# mcu.net
KiCad netlist of a schematic drawn in Altium Designer
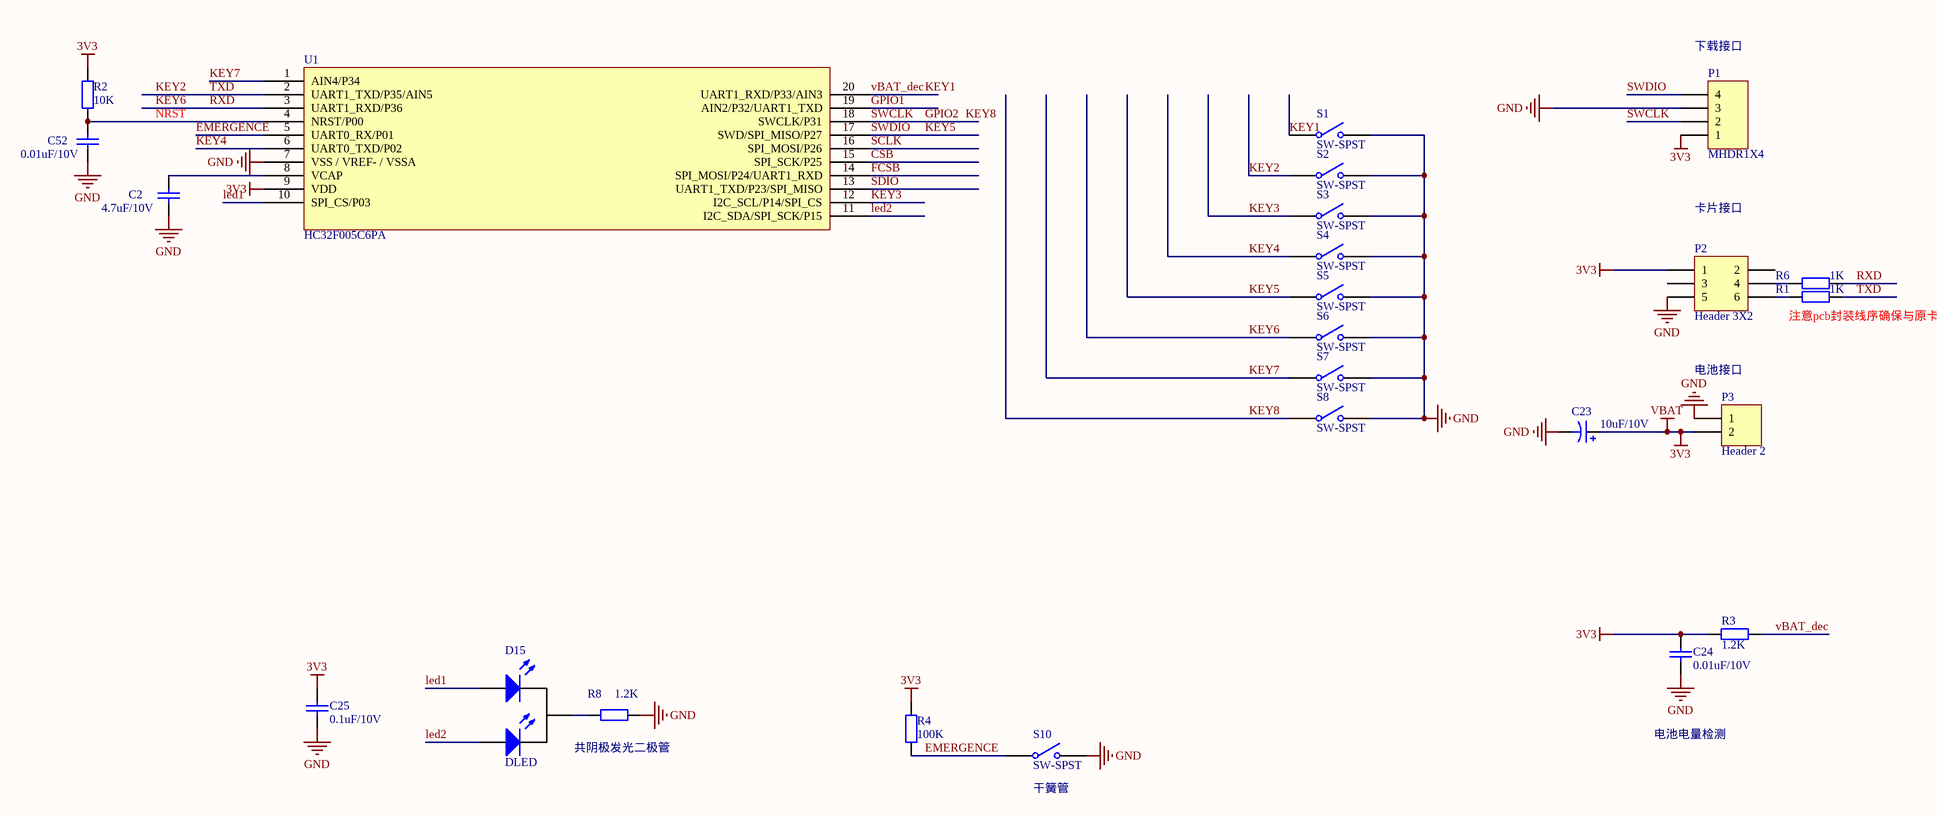
[diagram p0: mcu.SchDoc]

(export (version "E")
  (design (tool "Eeschema 10.0.6"))
  (components
    (comp (ref "C2")
      (value "4.7uF/10V")
      (footprint "0603C")
      (description "Capacitor")
      (fields (field (name "PUBLISHER") "Altium Limited"))
      (libsource (lib "Miscellaneous Devices") (part "Cap"))
    )
    (comp (ref "C23")
      (value "10uF/10V")
      (description "Polarized Capacitor (Radial)")
      (fields (field (name "PUBLISHER") "Altium Limited"))
      (libsource (lib "Miscellaneous Devices") (part "Cap Pol1"))
    )
    (comp (ref "C24")
      (value "0.01uF/10V")
      (footprint "0603C")
      (description "Capacitor")
      (fields (field (name "PUBLISHER") "Altium Limited"))
      (libsource (lib "Miscellaneous Devices") (part "Cap"))
    )
    (comp (ref "C25")
      (value "0.1uF/10V")
      (footprint "0603C")
      (description "Capacitor")
      (fields (field (name "PUBLISHER") "Altium Limited"))
      (libsource (lib "Miscellaneous Devices") (part "Cap"))
    )
    (comp (ref "C52")
      (value "0.01uF/10V")
      (footprint "0603C")
      (description "Capacitor")
      (fields (field (name "PUBLISHER") "Altium Limited"))
      (libsource (lib "Miscellaneous Devices") (part "Cap"))
    )
    (comp (ref "D15") (value "DLED") (libsource (lib "Schlib_20110825") (part "DLED")))
    (comp (ref "P1")
      (value "MHDR1X4")
      (footprint "SIP4")
      (description "Header, 4-Pin")
      (fields (field (name "PUBLISHER") "Altium Limited"))
      (libsource (lib "Miscellaneous Connectors") (part "MHDR1X4"))
    )
    (comp (ref "P2")
      (value "Header 3X2")
      (description "Header, 3-Pin, Dual row")
      (fields (field (name "PUBLISHER") "Altium Limited"))
      (libsource (lib "Miscellaneous Connectors") (part "Header 3X2"))
    )
    (comp (ref "P3")
      (value "Header 2")
      (description "Header, 2-Pin")
      (fields (field (name "PUBLISHER") "Altium Limited"))
      (libsource (lib "Miscellaneous Connectors") (part "Header 2"))
    )
    (comp (ref "R1")
      (value "1K")
      (footprint "0603R")
      (description "Resistor")
      (fields (field (name "PUBLISHER") "Altium Limited"))
      (libsource (lib "") (part "Res2_1"))
    )
    (comp (ref "R2")
      (value "10K")
      (footprint "0603R")
      (description "Resistor")
      (fields (field (name "PUBLISHER") "Altium Limited"))
      (libsource (lib "") (part "Res2_2"))
    )
    (comp (ref "R3")
      (value "1.2K")
      (footprint "0603R")
      (description "Resistor")
      (fields (field (name "PUBLISHER") "Altium Limited"))
      (libsource (lib "") (part "Res2_1"))
    )
    (comp (ref "R4")
      (value "100K")
      (footprint "0603R")
      (description "Resistor")
      (fields (field (name "PUBLISHER") "Altium Limited"))
      (libsource (lib "Miscellaneous Devices") (part "Res2"))
    )
    (comp (ref "R6")
      (value "1K")
      (footprint "0603R")
      (description "Resistor")
      (fields (field (name "PUBLISHER") "Altium Limited"))
      (libsource (lib "") (part "Res2_1"))
    )
    (comp (ref "R8")
      (value "1.2K")
      (footprint "0603R")
      (description "Resistor")
      (fields (field (name "PUBLISHER") "Altium Limited"))
      (libsource (lib "") (part "Res2_1"))
    )
    (comp (ref "S1")
      (value "SW-SPST")
      (description "Single-Pole, Single-Throw Switch")
      (fields (field (name "PUBLISHER") "Altium Limited"))
      (libsource (lib "Miscellaneous Devices") (part "SW-SPST"))
    )
    (comp (ref "S2")
      (value "SW-SPST")
      (description "Single-Pole, Single-Throw Switch")
      (fields (field (name "PUBLISHER") "Altium Limited"))
      (libsource (lib "Miscellaneous Devices") (part "SW-SPST"))
    )
    (comp (ref "S3")
      (value "SW-SPST")
      (description "Single-Pole, Single-Throw Switch")
      (fields (field (name "PUBLISHER") "Altium Limited"))
      (libsource (lib "Miscellaneous Devices") (part "SW-SPST"))
    )
    (comp (ref "S4")
      (value "SW-SPST")
      (description "Single-Pole, Single-Throw Switch")
      (fields (field (name "PUBLISHER") "Altium Limited"))
      (libsource (lib "Miscellaneous Devices") (part "SW-SPST"))
    )
    (comp (ref "S5")
      (value "SW-SPST")
      (description "Single-Pole, Single-Throw Switch")
      (fields (field (name "PUBLISHER") "Altium Limited"))
      (libsource (lib "Miscellaneous Devices") (part "SW-SPST"))
    )
    (comp (ref "S6")
      (value "SW-SPST")
      (description "Single-Pole, Single-Throw Switch")
      (fields (field (name "PUBLISHER") "Altium Limited"))
      (libsource (lib "Miscellaneous Devices") (part "SW-SPST"))
    )
    (comp (ref "S7")
      (value "SW-SPST")
      (description "Single-Pole, Single-Throw Switch")
      (fields (field (name "PUBLISHER") "Altium Limited"))
      (libsource (lib "Miscellaneous Devices") (part "SW-SPST"))
    )
    (comp (ref "S8")
      (value "SW-SPST")
      (description "Single-Pole, Single-Throw Switch")
      (fields (field (name "PUBLISHER") "Altium Limited"))
      (libsource (lib "Miscellaneous Devices") (part "SW-SPST"))
    )
    (comp (ref "S10")
      (value "SW-SPST")
      (description "Single-Pole, Single-Throw Switch")
      (fields (field (name "PUBLISHER") "Altium Limited"))
      (libsource (lib "Miscellaneous Devices") (part "SW-SPST"))
    )
    (comp (ref "U1") (value "HC32F005C6PA") (libsource (lib "Schlib_20110825") (part "HC32F005C6PA")))
  )
  (nets
    (net (code "1") (name "/CSB") (class "Default")
      (node (ref "U1") (pin "15") (pinfunction "SPI_SCK/P25_15") (pintype "passive"))
    )
    (net (code "2") (name "/EMERGENCE") (class "Default")
      (node (ref "R4") (pin "2") (pinfunction "2_2") (pintype "passive"))
      (node (ref "S10") (pin "1") (pinfunction "COMMON_1") (pintype "passive"))
      (node (ref "U1") (pin "5") (pinfunction "UART0_RX/P01_5") (pintype "passive"))
    )
    (net (code "3") (name "/FCSB") (class "Default")
      (node (ref "U1") (pin "14") (pinfunction "SPI_MOSI/P24/UART1_RXD_14") (pintype "passive"))
    )
    (net (code "4") (name "/GPIO1") (class "Default")
      (node (ref "U1") (pin "19") (pinfunction "AIN2/P32/UART1_TXD_19") (pintype "passive"))
    )
    (net (code "5") (name "/GPIO2") (class "Default")
      (node (ref "P1") (pin "2") (pinfunction "2_2") (pintype "passive"))
      (node (ref "S8") (pin "1") (pinfunction "COMMON_1") (pintype "passive"))
      (node (ref "U1") (pin "18") (pinfunction "SWCLK/P31_18") (pintype "passive"))
    )
    (net (code "6") (name "/KEY1") (class "Default")
      (node (ref "R3") (pin "1") (pinfunction "1_1") (pintype "passive"))
      (node (ref "S1") (pin "1") (pinfunction "COMMON_1") (pintype "passive"))
      (node (ref "U1") (pin "20") (pinfunction "UART1_RXD/P33/AIN3_20") (pintype "passive"))
    )
    (net (code "7") (name "/KEY2") (class "Default")
      (node (ref "R1") (pin "1") (pinfunction "1_1") (pintype "passive"))
      (node (ref "S2") (pin "1") (pinfunction "COMMON_1") (pintype "passive"))
      (node (ref "U1") (pin "2") (pinfunction "UART1_TXD/P35/AIN5_2") (pintype "passive"))
    )
    (net (code "8") (name "/KEY3") (class "Default")
      (node (ref "S3") (pin "1") (pinfunction "COMMON_1") (pintype "passive"))
      (node (ref "U1") (pin "12") (pinfunction "I2C_SCL/P14/SPI_CS_12") (pintype "passive"))
    )
    (net (code "9") (name "/KEY4") (class "Default")
      (node (ref "S4") (pin "1") (pinfunction "COMMON_1") (pintype "passive"))
      (node (ref "U1") (pin "6") (pinfunction "UART0_TXD/P02_6") (pintype "passive"))
    )
    (net (code "10") (name "/KEY5") (class "Default")
      (node (ref "P1") (pin "4") (pinfunction "4_4") (pintype "passive"))
      (node (ref "S5") (pin "1") (pinfunction "COMMON_1") (pintype "passive"))
      (node (ref "U1") (pin "17") (pinfunction "SWD/SPI_MISO/P27_17") (pintype "passive"))
    )
    (net (code "11") (name "/KEY6") (class "Default")
      (node (ref "R6") (pin "1") (pinfunction "1_1") (pintype "passive"))
      (node (ref "S6") (pin "1") (pinfunction "COMMON_1") (pintype "passive"))
      (node (ref "U1") (pin "3") (pinfunction "UART1_RXD/P36_3") (pintype "passive"))
    )
    (net (code "12") (name "/KEY7") (class "Default")
      (node (ref "S7") (pin "1") (pinfunction "COMMON_1") (pintype "passive"))
      (node (ref "U1") (pin "1") (pinfunction "AIN4/P34_1") (pintype "passive"))
    )
    (net (code "13") (name "/NRST") (class "Default")
      (node (ref "C52") (pin "1") (pinfunction "1_1") (pintype "passive"))
      (node (ref "R2") (pin "1") (pinfunction "1_1") (pintype "passive"))
      (node (ref "U1") (pin "4") (pinfunction "NRST/P00_4") (pintype "passive"))
    )
    (net (code "14") (name "/SCLK") (class "Default")
      (node (ref "U1") (pin "16") (pinfunction "SPI_MOSI/P26_16") (pintype "passive"))
    )
    (net (code "15") (name "/SDIO") (class "Default")
      (node (ref "U1") (pin "13") (pinfunction "UART1_TXD/P23/SPI_MISO_13") (pintype "passive"))
    )
    (net (code "16") (name "/led1") (class "Default")
      (node (ref "D15") (pin "1") (pinfunction "A_1") (pintype "passive"))
      (node (ref "U1") (pin "10") (pinfunction "SPI_CS/P03_10") (pintype "passive"))
    )
    (net (code "17") (name "/led2") (class "Default")
      (node (ref "D15") (pin "3") (pinfunction "A_3") (pintype "passive"))
      (node (ref "U1") (pin "11") (pinfunction "I2C_SDA/SPI_SCK/P15_11") (pintype "passive"))
    )
    (net (code "18") (name "3V3") (class "Default")
      (node (ref "C23") (pin "1") (pinfunction "1_1") (pintype "passive"))
      (node (ref "C24") (pin "1") (pinfunction "1_1") (pintype "passive"))
      (node (ref "C25") (pin "1") (pinfunction "1_1") (pintype "passive"))
      (node (ref "P1") (pin "1") (pinfunction "1_1") (pintype "passive"))
      (node (ref "P2") (pin "1") (pinfunction "1_1") (pintype "passive"))
      (node (ref "P3") (pin "2") (pinfunction "2_2") (pintype "passive"))
      (node (ref "R2") (pin "2") (pinfunction "2_2") (pintype "passive"))
      (node (ref "R3") (pin "2") (pinfunction "2_2") (pintype "passive"))
      (node (ref "R4") (pin "1") (pinfunction "1_1") (pintype "passive"))
      (node (ref "U1") (pin "9") (pinfunction "VDD_9") (pintype "passive"))
    )
    (net (code "19") (name "GND") (class "Default")
      (node (ref "C2") (pin "2") (pinfunction "2_2") (pintype "passive"))
      (node (ref "C23") (pin "2") (pinfunction "2_2") (pintype "passive"))
      (node (ref "C24") (pin "2") (pinfunction "2_2") (pintype "passive"))
      (node (ref "C25") (pin "2") (pinfunction "2_2") (pintype "passive"))
      (node (ref "C52") (pin "2") (pinfunction "2_2") (pintype "passive"))
      (node (ref "P1") (pin "3") (pinfunction "3_3") (pintype "passive"))
      (node (ref "P2") (pin "5") (pinfunction "5_5") (pintype "passive"))
      (node (ref "P3") (pin "1") (pinfunction "1_1") (pintype "passive"))
      (node (ref "R8") (pin "1") (pinfunction "1_1") (pintype "passive"))
      (node (ref "S1") (pin "2") (pinfunction "NO_2") (pintype "passive"))
      (node (ref "S10") (pin "2") (pinfunction "NO_2") (pintype "passive"))
      (node (ref "S2") (pin "2") (pinfunction "NO_2") (pintype "passive"))
      (node (ref "S3") (pin "2") (pinfunction "NO_2") (pintype "passive"))
      (node (ref "S4") (pin "2") (pinfunction "NO_2") (pintype "passive"))
      (node (ref "S5") (pin "2") (pinfunction "NO_2") (pintype "passive"))
      (node (ref "S6") (pin "2") (pinfunction "NO_2") (pintype "passive"))
      (node (ref "S7") (pin "2") (pinfunction "NO_2") (pintype "passive"))
      (node (ref "S8") (pin "2") (pinfunction "NO_2") (pintype "passive"))
      (node (ref "U1") (pin "7") (pinfunction "VSS_/_VREF-_/_VSSA_7") (pintype "passive"))
    )
    (net (code "20") (name "Net-(D15-K)") (class "Default")
      (node (ref "D15") (pin "2") (pinfunction "K_2") (pintype "passive"))
      (node (ref "R8") (pin "2") (pinfunction "2_2") (pintype "passive"))
    )
    (net (code "21") (name "Net-(P2-Pad4)") (class "Default")
      (node (ref "P2") (pin "4") (pinfunction "4_4") (pintype "passive"))
      (node (ref "R6") (pin "2") (pinfunction "2_2") (pintype "passive"))
    )
    (net (code "22") (name "Net-(P2-Pad6)") (class "Default")
      (node (ref "P2") (pin "6") (pinfunction "6_6") (pintype "passive"))
      (node (ref "R1") (pin "2") (pinfunction "2_2") (pintype "passive"))
    )
    (net (code "23") (name "Net-(U1-VCAP)") (class "Default")
      (node (ref "C2") (pin "1") (pinfunction "1_1") (pintype "passive"))
      (node (ref "U1") (pin "8") (pinfunction "VCAP_8") (pintype "passive"))
    )
    (net (code "24") (name "unconnected-(P2-Pad2)") (class "Default")
      (node (ref "P2") (pin "2") (pinfunction "2_2") (pintype "passive"))
    )
    (net (code "25") (name "unconnected-(P2-Pad3)") (class "Default")
      (node (ref "P2") (pin "3") (pinfunction "3_3") (pintype "passive"))
    )
  )
)
